# main.net
KiCad netlist of a schematic drawn in Altium Designer
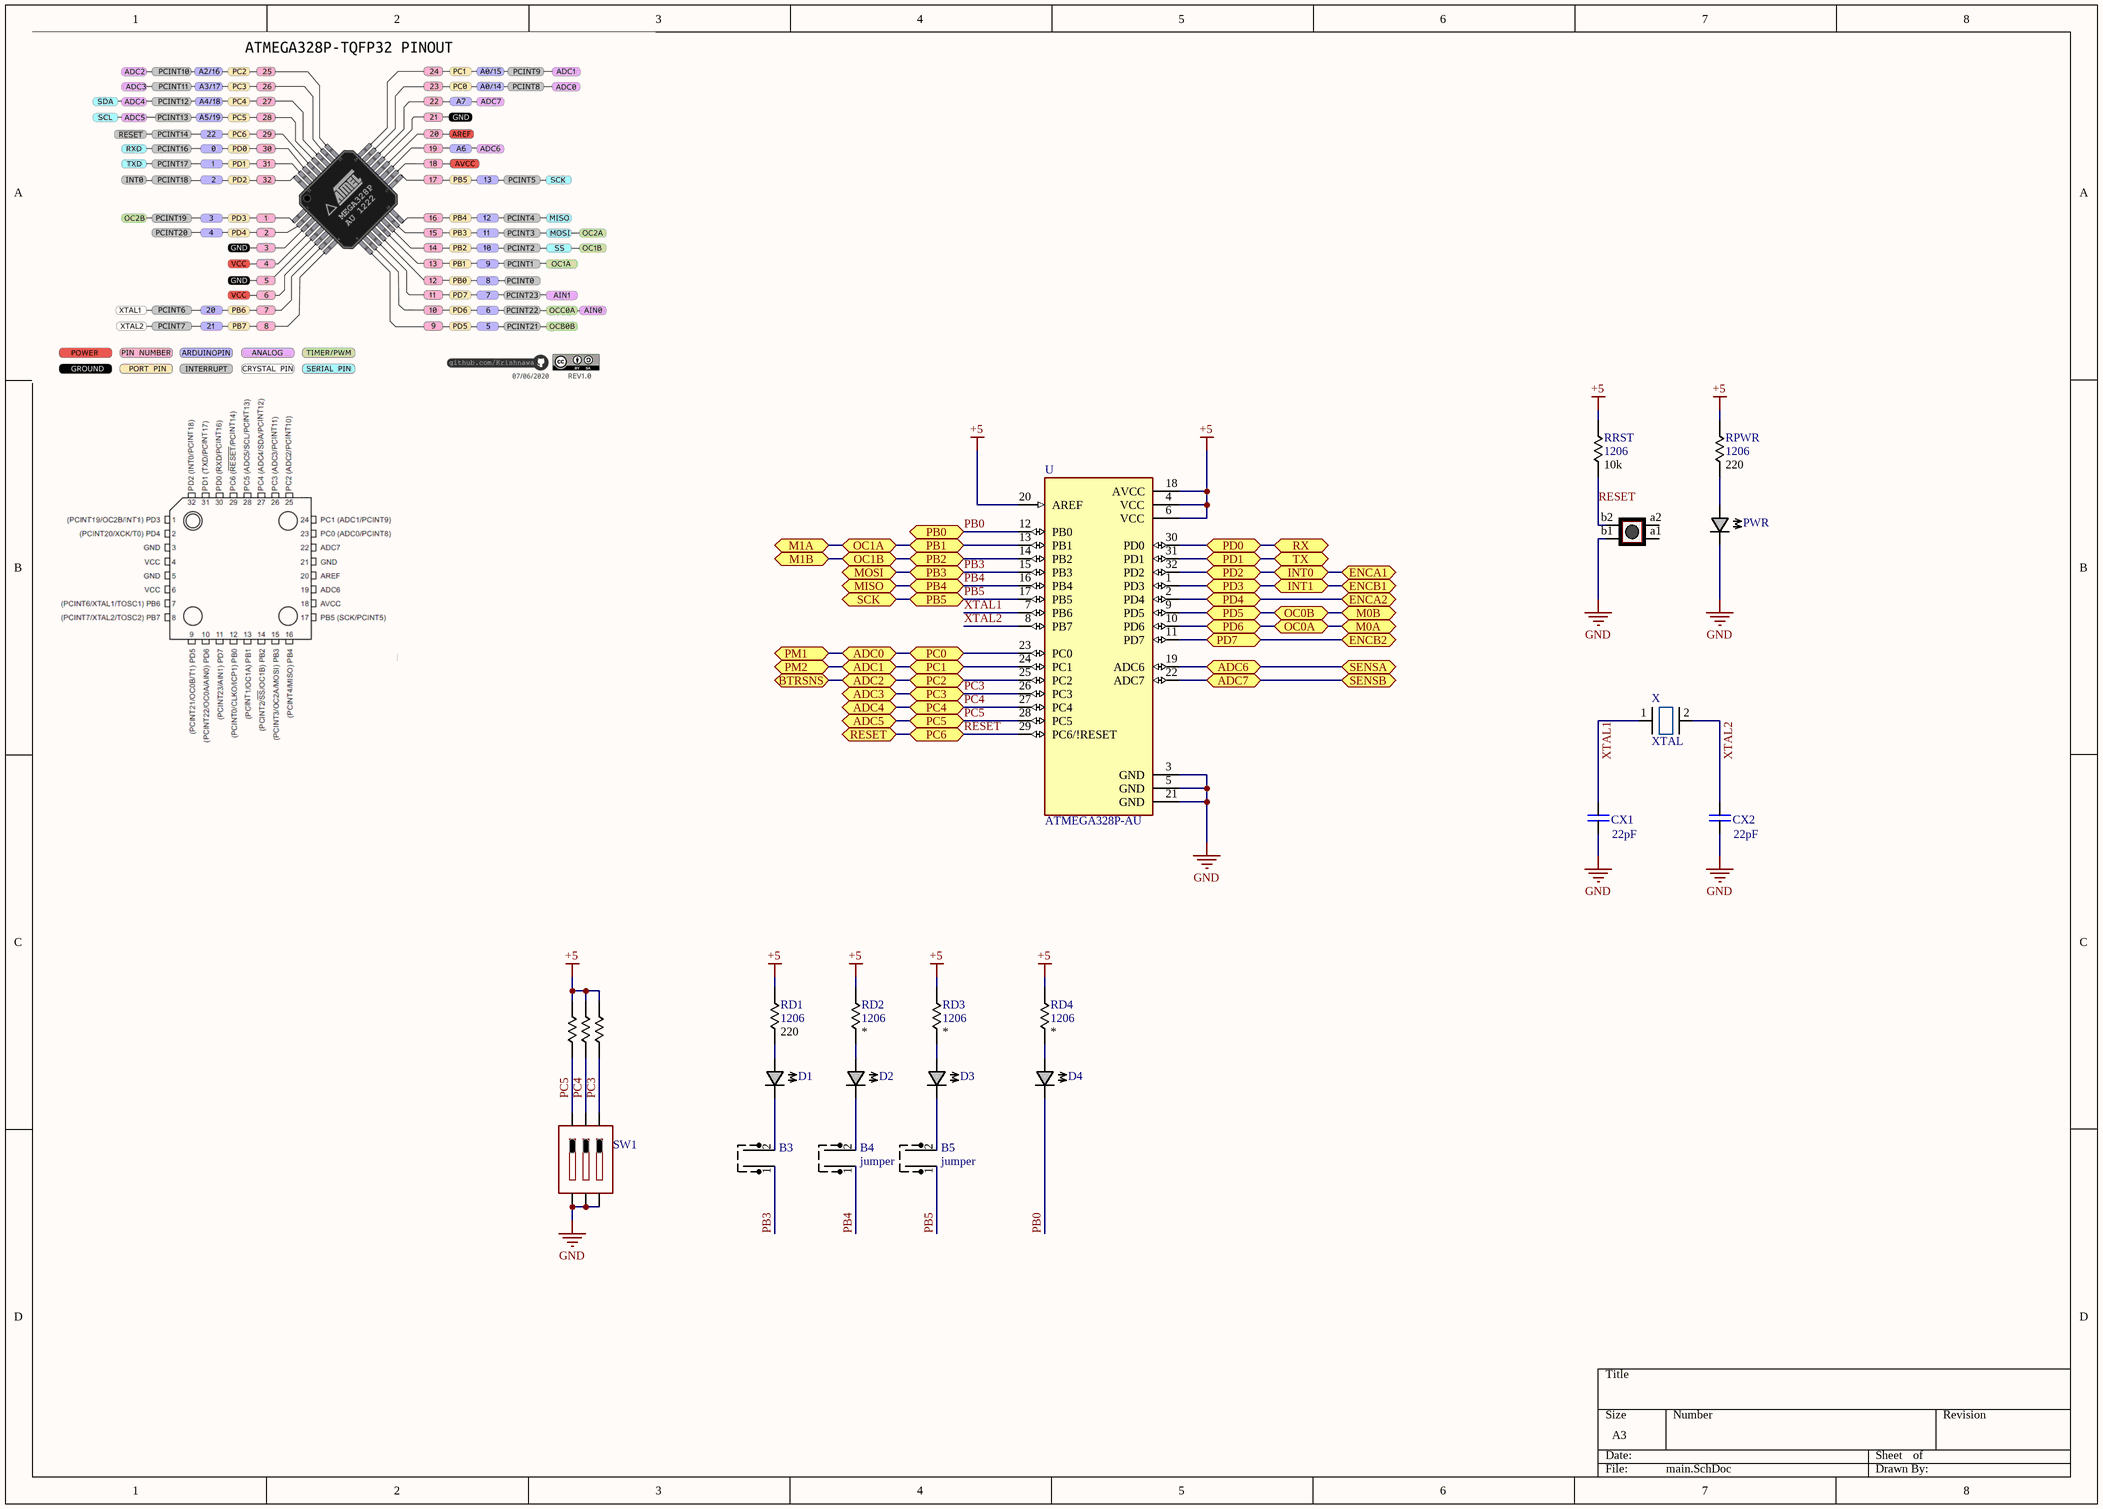
[diagram p0: main.SchDoc]

(export (version "E")
  (design (tool "Eeschema 10.0.6"))
  (components
    (comp (ref "B3") (value "jumper") (footprint "JUMPER2") (libsource (lib "JUMPER2") (part "Jumper_2")))
    (comp (ref "B4") (value "jumper") (footprint "JUMPER2") (libsource (lib "JUMPER2") (part "Jumper_2")))
    (comp (ref "B5") (value "jumper") (footprint "JUMPER2") (libsource (lib "JUMPER2") (part "Jumper_2")))
    (comp (ref "CX1")
      (value "22pF")
      (footprint "cap100")
      (fields (field (name "Comment") "cap disk"))
      (libsource (lib "CAP_100th") (part "C?"))
    )
    (comp (ref "CX2")
      (value "22pF")
      (footprint "cap100")
      (fields (field (name "Comment") "cap disk"))
      (libsource (lib "CAP_100th") (part "C?"))
    )
    (comp (ref "D1") (value "3.2x1.6") (footprint "LED3_2X1_6") (libsource (lib "LED_3d2_1d6") (part "led")))
    (comp (ref "D2") (value "3.2x1.6") (footprint "LED3_2X1_6") (libsource (lib "LED_3d2_1d6") (part "led")))
    (comp (ref "D3") (value "3.2x1.6") (footprint "LED3_2X1_6") (libsource (lib "LED_3d2_1d6") (part "led")))
    (comp (ref "D4") (value "3.2x1.6") (footprint "LED3_2X1_6") (libsource (lib "LED_3d2_1d6") (part "led")))
    (comp (ref "PWR") (value "3.2x1.6") (footprint "LED3_2X1_6") (libsource (lib "LED_3d2_1d6") (part "led")))
    (comp (ref "RD1")
      (value "1206")
      (footprint "1206")
      (fields (field (name "ALTIUM_VALUE") "220"))
      (libsource (lib "Res_3_2__1_6") (part "1206"))
    )
    (comp (ref "RD2")
      (value "1206")
      (footprint "1206")
      (fields (field (name "ALTIUM_VALUE") "*"))
      (libsource (lib "Res_3_2__1_6") (part "1206"))
    )
    (comp (ref "RD3")
      (value "1206")
      (footprint "1206")
      (fields (field (name "ALTIUM_VALUE") "*"))
      (libsource (lib "Res_3_2__1_6") (part "1206"))
    )
    (comp (ref "RD4")
      (value "1206")
      (footprint "1206")
      (fields (field (name "ALTIUM_VALUE") "*"))
      (libsource (lib "Res_3_2__1_6") (part "1206"))
    )
    (comp (ref "RPWR")
      (value "1206")
      (footprint "1206")
      (fields (field (name "ALTIUM_VALUE") "220"))
      (libsource (lib "Res_3_2__1_6") (part "1206"))
    )
    (comp (ref "RRST")
      (value "1206")
      (footprint "1206")
      (fields (field (name "ALTIUM_VALUE") "10k"))
      (libsource (lib "Res_3_2__1_6") (part "1206"))
    )
    (comp (ref "RST_SW")
      (value "button")
      (footprint "push_button")
      (libsource (lib "push_button") (part "button"))
    )
    (comp (ref "RSW1") (value "1206") (footprint "1206") (libsource (lib "Res_3_2__1_6") (part "1206")))
    (comp (ref "RSW2") (value "1206") (footprint "1206") (libsource (lib "Res_3_2__1_6") (part "1206")))
    (comp (ref "RSW3") (value "1206") (footprint "1206") (libsource (lib "Res_3_2__1_6") (part "1206")))
    (comp (ref "SW1")
      (value "dipsw3")
      (footprint "PCBComponent_1")
      (libsource (lib "dip_switch_3p") (part "dipsw3"))
    )
    (comp (ref "U")
      (value "ATMEGA328P-AU")
      (footprint "QFP80P900X900X120-32N")
      (description "AVR AVRÂ® ATmega Microcontroller IC 8-Bit 20MHz 32KB _16K x 16_ FLASH 32-TQFP _7x7_")
      (fields (field (name "MF") "Microchip"))
      (libsource (lib "atmega328p") (part "ATMEGA328P-AU"))
    )
    (comp (ref "X") (value "XTAL") (footprint "XTAL1") (libsource (lib "XTAL") (part "XTAL")))
  )
  (nets
    (net (code "1") (name "+5") (class "Default")
      (node (ref "RD1") (pin "2") (pinfunction "2_2") (pintype "passive"))
      (node (ref "RD2") (pin "2") (pinfunction "2_2") (pintype "passive"))
      (node (ref "RD3") (pin "2") (pinfunction "2_2") (pintype "passive"))
      (node (ref "RD4") (pin "2") (pinfunction "2_2") (pintype "passive"))
      (node (ref "RPWR") (pin "2") (pinfunction "2_2") (pintype "passive"))
      (node (ref "RRST") (pin "2") (pinfunction "2_2") (pintype "passive"))
      (node (ref "RSW1") (pin "2") (pinfunction "2_2") (pintype "passive"))
      (node (ref "RSW2") (pin "2") (pinfunction "2_2") (pintype "passive"))
      (node (ref "RSW3") (pin "2") (pinfunction "2_2") (pintype "passive"))
      (node (ref "U") (pin "18") (pinfunction "AVCC_18") (pintype "power_in"))
      (node (ref "U") (pin "20") (pinfunction "AREF_20") (pintype "input"))
      (node (ref "U") (pin "4") (pinfunction "VCC_4") (pintype "power_in"))
      (node (ref "U") (pin "6") (pinfunction "VCC_6") (pintype "power_in"))
    )
    (net (code "2") (name "/ADC0") (class "Default")
      (node (ref "U") (pin "23") (pinfunction "PC0_23") (pintype "bidirectional"))
    )
    (net (code "3") (name "/ADC1") (class "Default")
      (node (ref "U") (pin "24") (pinfunction "PC1_24") (pintype "bidirectional"))
    )
    (net (code "4") (name "/ADC2") (class "Default")
      (node (ref "U") (pin "25") (pinfunction "PC2_25") (pintype "bidirectional"))
    )
    (net (code "5") (name "/ADC6") (class "Default")
      (node (ref "U") (pin "19") (pinfunction "ADC6_19") (pintype "bidirectional"))
    )
    (net (code "6") (name "/ADC7") (class "Default")
      (node (ref "U") (pin "22") (pinfunction "ADC7_22") (pintype "bidirectional"))
    )
    (net (code "7") (name "/ENCA1") (class "Default")
      (node (ref "U") (pin "32") (pinfunction "PD2_32") (pintype "bidirectional"))
    )
    (net (code "8") (name "/ENCA2") (class "Default")
      (node (ref "U") (pin "2") (pinfunction "PD4_2") (pintype "bidirectional"))
    )
    (net (code "9") (name "/ENCB1") (class "Default")
      (node (ref "U") (pin "1") (pinfunction "PD3_1") (pintype "bidirectional"))
    )
    (net (code "10") (name "/ENCB2") (class "Default")
      (node (ref "U") (pin "11") (pinfunction "PD7_11") (pintype "bidirectional"))
    )
    (net (code "11") (name "/M0A") (class "Default")
      (node (ref "U") (pin "10") (pinfunction "PD6_10") (pintype "bidirectional"))
    )
    (net (code "12") (name "/M0B") (class "Default")
      (node (ref "U") (pin "9") (pinfunction "PD5_9") (pintype "bidirectional"))
    )
    (net (code "13") (name "/M1A") (class "Default")
      (node (ref "U") (pin "13") (pinfunction "PB1_13") (pintype "bidirectional"))
    )
    (net (code "14") (name "/M1B") (class "Default")
      (node (ref "U") (pin "14") (pinfunction "PB2_14") (pintype "bidirectional"))
    )
    (net (code "15") (name "/PB0") (class "Default")
      (node (ref "D4") (pin "C") (pinfunction "C_C") (pintype "passive"))
      (node (ref "U") (pin "12") (pinfunction "PB0_12") (pintype "bidirectional"))
    )
    (net (code "16") (name "/PB3") (class "Default")
      (node (ref "B3") (pin "1") (pinfunction "1_1") (pintype "passive"))
      (node (ref "U") (pin "15") (pinfunction "PB3_15") (pintype "bidirectional"))
    )
    (net (code "17") (name "/PB4") (class "Default")
      (node (ref "B4") (pin "1") (pinfunction "1_1") (pintype "passive"))
      (node (ref "U") (pin "16") (pinfunction "PB4_16") (pintype "bidirectional"))
    )
    (net (code "18") (name "/PB5") (class "Default")
      (node (ref "B5") (pin "1") (pinfunction "1_1") (pintype "passive"))
      (node (ref "U") (pin "17") (pinfunction "PB5_17") (pintype "bidirectional"))
    )
    (net (code "19") (name "/PC3") (class "Default")
      (node (ref "RSW3") (pin "1") (pinfunction "1_1") (pintype "passive"))
      (node (ref "SW1") (pin "1") (pinfunction "1_1") (pintype "passive"))
      (node (ref "U") (pin "26") (pinfunction "PC3_26") (pintype "bidirectional"))
    )
    (net (code "20") (name "/PC4") (class "Default")
      (node (ref "RSW2") (pin "1") (pinfunction "1_1") (pintype "passive"))
      (node (ref "SW1") (pin "2") (pinfunction "2_2") (pintype "passive"))
      (node (ref "U") (pin "27") (pinfunction "PC4_27") (pintype "bidirectional"))
    )
    (net (code "21") (name "/PC5") (class "Default")
      (node (ref "RSW1") (pin "1") (pinfunction "1_1") (pintype "passive"))
      (node (ref "SW1") (pin "3") (pinfunction "3_3") (pintype "passive"))
      (node (ref "U") (pin "28") (pinfunction "PC5_28") (pintype "bidirectional"))
    )
    (net (code "22") (name "/PD0") (class "Default")
      (node (ref "U") (pin "30") (pinfunction "PD0_30") (pintype "bidirectional"))
    )
    (net (code "23") (name "/PD1") (class "Default")
      (node (ref "U") (pin "31") (pinfunction "PD1_31") (pintype "bidirectional"))
    )
    (net (code "24") (name "/RESET") (class "Default")
      (node (ref "RRST") (pin "1") (pinfunction "1_1") (pintype "passive"))
      (node (ref "RST_SW") (pin "b2") (pinfunction "b2_b2") (pintype "passive"))
      (node (ref "U") (pin "29") (pinfunction "PC6/!RESET_29") (pintype "bidirectional"))
    )
    (net (code "25") (name "/XTAL1") (class "Default")
      (node (ref "CX1") (pin "2") (pinfunction "2_2") (pintype "passive"))
      (node (ref "U") (pin "7") (pinfunction "PB6_7") (pintype "bidirectional"))
      (node (ref "X") (pin "1") (pinfunction "1_1") (pintype "passive"))
    )
    (net (code "26") (name "/XTAL2") (class "Default")
      (node (ref "CX2") (pin "2") (pinfunction "2_2") (pintype "passive"))
      (node (ref "U") (pin "8") (pinfunction "PB7_8") (pintype "bidirectional"))
      (node (ref "X") (pin "2") (pinfunction "2_2") (pintype "passive"))
    )
    (net (code "27") (name "GND") (class "Default")
      (node (ref "CX1") (pin "1") (pinfunction "1_1") (pintype "passive"))
      (node (ref "CX2") (pin "1") (pinfunction "1_1") (pintype "passive"))
      (node (ref "PWR") (pin "C") (pinfunction "C_C") (pintype "passive"))
      (node (ref "RST_SW") (pin "b1") (pinfunction "b1_b1") (pintype "passive"))
      (node (ref "SW1") (pin "4") (pinfunction "4_4") (pintype "passive"))
      (node (ref "SW1") (pin "5") (pinfunction "5_5") (pintype "passive"))
      (node (ref "SW1") (pin "6") (pinfunction "6_6") (pintype "passive"))
      (node (ref "U") (pin "21") (pinfunction "GND_21") (pintype "power_in"))
      (node (ref "U") (pin "3") (pinfunction "GND_3") (pintype "power_in"))
      (node (ref "U") (pin "5") (pinfunction "GND_5") (pintype "power_in"))
    )
    (net (code "28") (name "Net-(B3-Pad2)") (class "Default")
      (node (ref "B3") (pin "2") (pinfunction "2_2") (pintype "passive"))
      (node (ref "D1") (pin "C") (pinfunction "C_C") (pintype "passive"))
    )
    (net (code "29") (name "Net-(B4-Pad2)") (class "Default")
      (node (ref "B4") (pin "2") (pinfunction "2_2") (pintype "passive"))
      (node (ref "D2") (pin "C") (pinfunction "C_C") (pintype "passive"))
    )
    (net (code "30") (name "Net-(B5-Pad2)") (class "Default")
      (node (ref "B5") (pin "2") (pinfunction "2_2") (pintype "passive"))
      (node (ref "D3") (pin "C") (pinfunction "C_C") (pintype "passive"))
    )
    (net (code "31") (name "Net-(D1-PadA)") (class "Default")
      (node (ref "D1") (pin "A") (pinfunction "A_A") (pintype "passive"))
      (node (ref "RD1") (pin "1") (pinfunction "1_1") (pintype "passive"))
    )
    (net (code "32") (name "Net-(D2-PadA)") (class "Default")
      (node (ref "D2") (pin "A") (pinfunction "A_A") (pintype "passive"))
      (node (ref "RD2") (pin "1") (pinfunction "1_1") (pintype "passive"))
    )
    (net (code "33") (name "Net-(D3-PadA)") (class "Default")
      (node (ref "D3") (pin "A") (pinfunction "A_A") (pintype "passive"))
      (node (ref "RD3") (pin "1") (pinfunction "1_1") (pintype "passive"))
    )
    (net (code "34") (name "Net-(D4-PadA)") (class "Default")
      (node (ref "D4") (pin "A") (pinfunction "A_A") (pintype "passive"))
      (node (ref "RD4") (pin "1") (pinfunction "1_1") (pintype "passive"))
    )
    (net (code "35") (name "Net-(PWR-PadA)") (class "Default")
      (node (ref "PWR") (pin "A") (pinfunction "A_A") (pintype "passive"))
      (node (ref "RPWR") (pin "1") (pinfunction "1_1") (pintype "passive"))
    )
    (net (code "36") (name "unconnected-(RST_SW-Pada1)") (class "Default")
      (node (ref "RST_SW") (pin "a1") (pinfunction "a1_a1") (pintype "passive"))
    )
    (net (code "37") (name "unconnected-(RST_SW-Pada2)") (class "Default")
      (node (ref "RST_SW") (pin "a2") (pinfunction "a2_a2") (pintype "passive"))
    )
  )
)
